# untitled.net
KiCad netlist of a schematic drawn in EAGLE
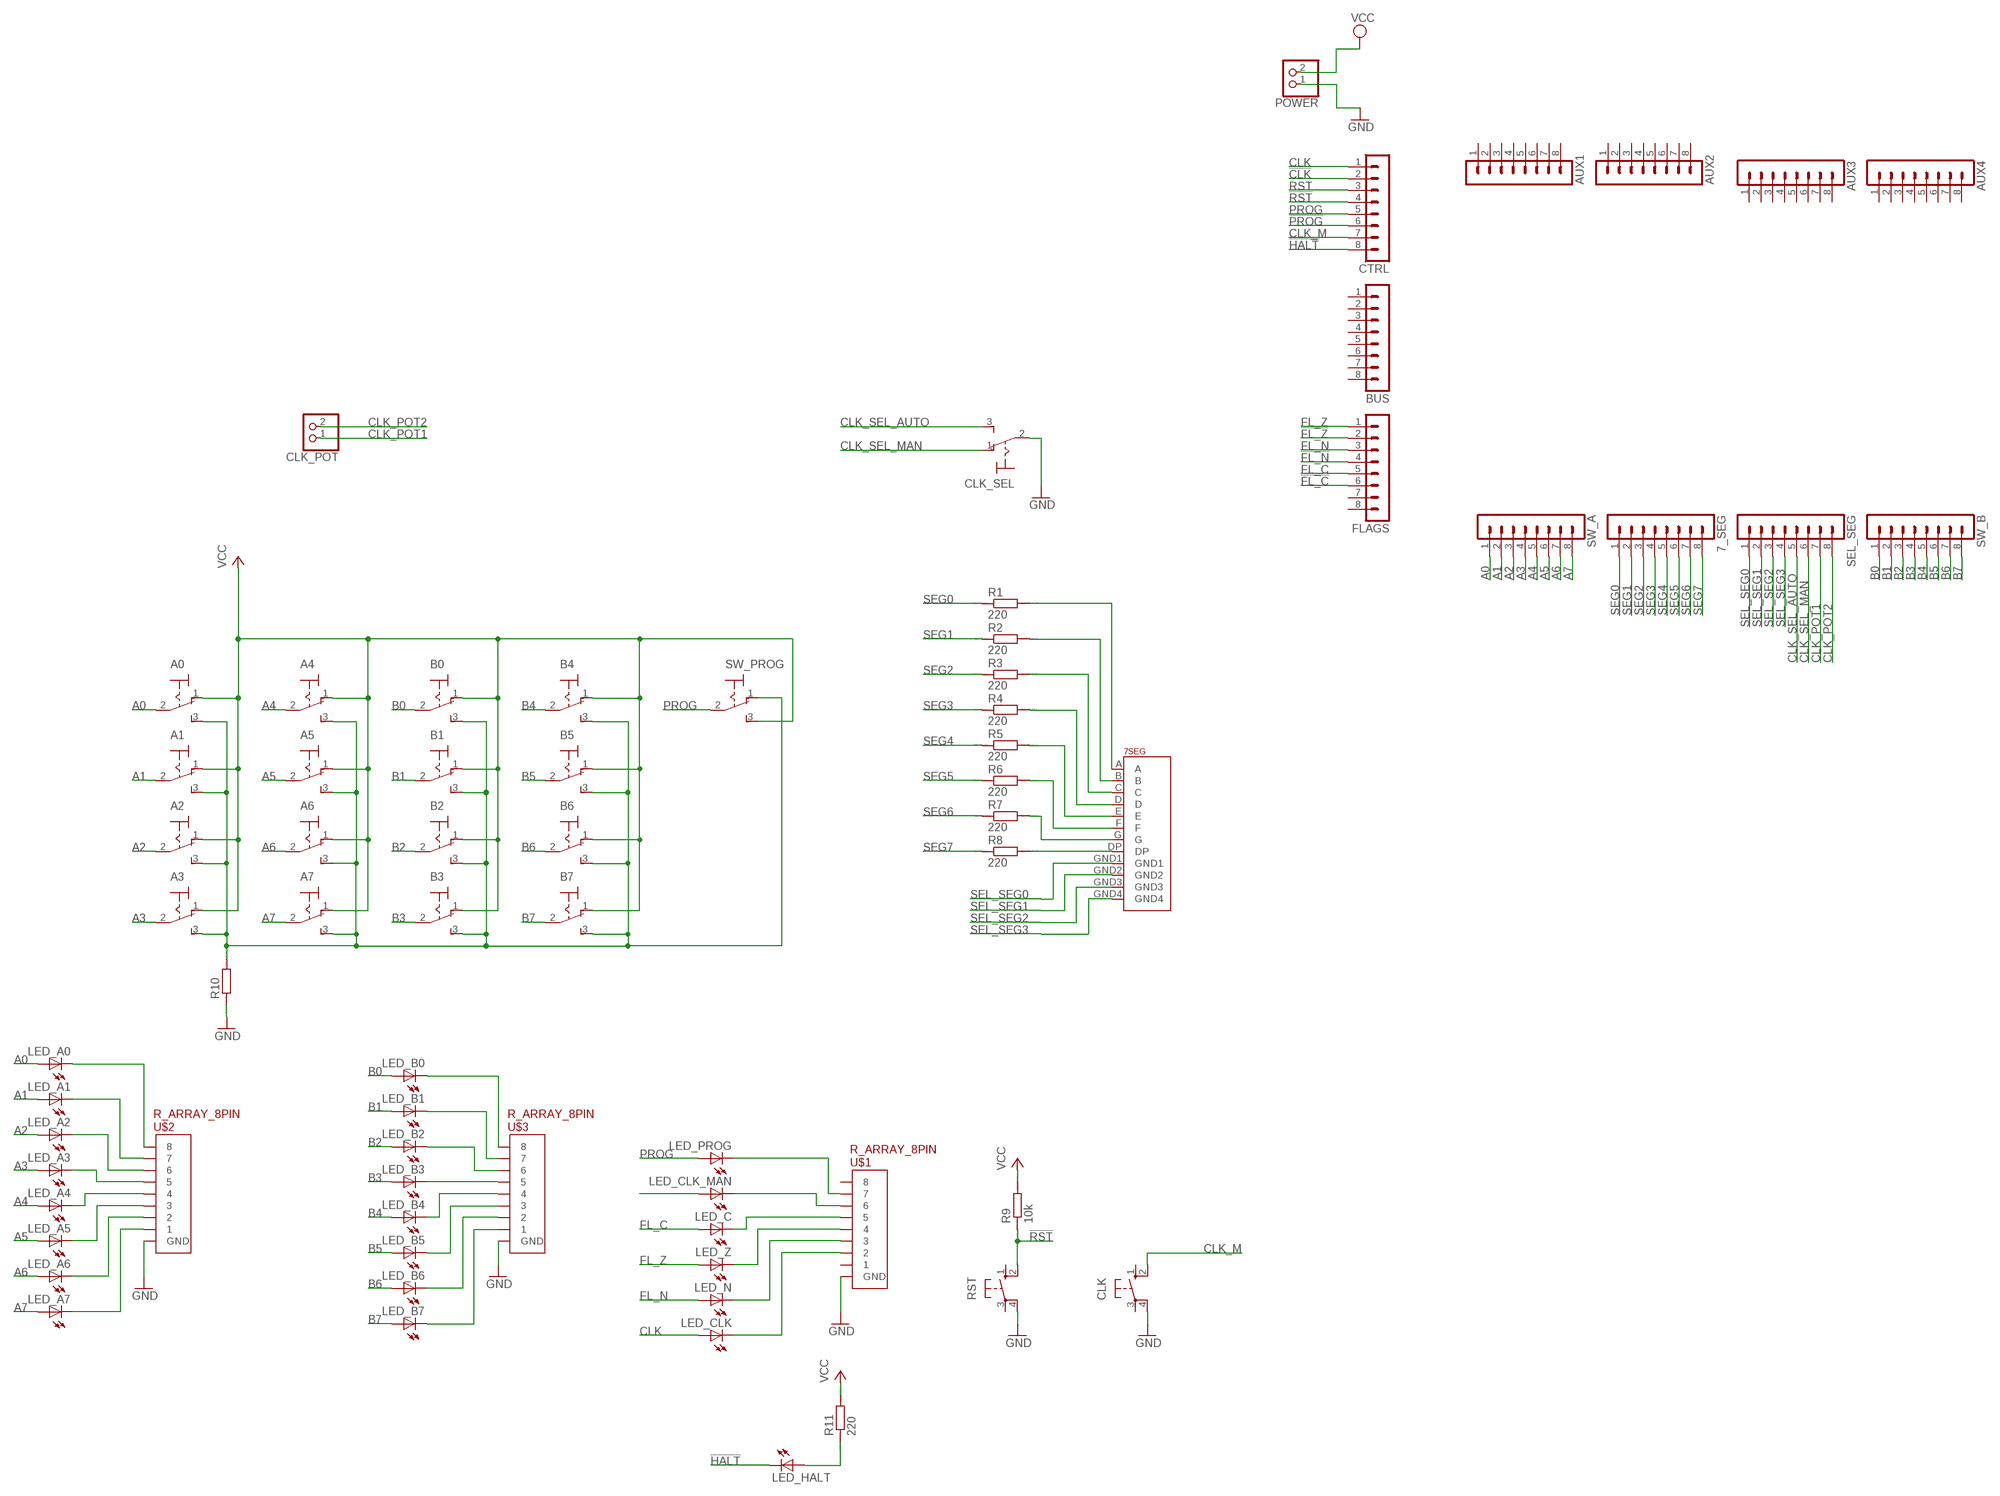
[diagram p0: schematic, sheet 1]

(export (version "E")
  (design (tool "Eeschema 10.0.6"))
  (components
    (comp (ref "7SEG")
      (value "7SEGX4")
      (footprint "eagle-import:7SEGX4")
      (libsource (lib "eagle-import") (part "7SEGX4"))
    )
    (comp (ref "7_SEG")
      (value "MA08-1")
      (footprint "eagle-import:MA08-1")
      (libsource (lib "eagle-import") (part "MA08-1"))
    )
    (comp (ref "A0")
      (value "M9040P")
      (footprint "eagle-import:M9040P")
      (libsource (lib "eagle-import") (part "M9040P"))
    )
    (comp (ref "A1")
      (value "M9040P")
      (footprint "eagle-import:M9040P")
      (libsource (lib "eagle-import") (part "M9040P"))
    )
    (comp (ref "A2")
      (value "M9040P")
      (footprint "eagle-import:M9040P")
      (libsource (lib "eagle-import") (part "M9040P"))
    )
    (comp (ref "A3")
      (value "M9040P")
      (footprint "eagle-import:M9040P")
      (libsource (lib "eagle-import") (part "M9040P"))
    )
    (comp (ref "A4")
      (value "M9040P")
      (footprint "eagle-import:M9040P")
      (libsource (lib "eagle-import") (part "M9040P"))
    )
    (comp (ref "A5")
      (value "M9040P")
      (footprint "eagle-import:M9040P")
      (libsource (lib "eagle-import") (part "M9040P"))
    )
    (comp (ref "A6")
      (value "M9040P")
      (footprint "eagle-import:M9040P")
      (libsource (lib "eagle-import") (part "M9040P"))
    )
    (comp (ref "A7")
      (value "M9040P")
      (footprint "eagle-import:M9040P")
      (libsource (lib "eagle-import") (part "M9040P"))
    )
    (comp (ref "AUX1")
      (value "MA08-1")
      (footprint "eagle-import:MA08-1")
      (libsource (lib "eagle-import") (part "MA08-1"))
    )
    (comp (ref "AUX2")
      (value "MA08-1")
      (footprint "eagle-import:MA08-1")
      (libsource (lib "eagle-import") (part "MA08-1"))
    )
    (comp (ref "AUX3")
      (value "MA08-1")
      (footprint "eagle-import:MA08-1")
      (libsource (lib "eagle-import") (part "MA08-1"))
    )
    (comp (ref "AUX4")
      (value "MA08-1")
      (footprint "eagle-import:MA08-1")
      (libsource (lib "eagle-import") (part "MA08-1"))
    )
    (comp (ref "B0")
      (value "M9040P")
      (footprint "eagle-import:M9040P")
      (libsource (lib "eagle-import") (part "M9040P"))
    )
    (comp (ref "B1")
      (value "M9040P")
      (footprint "eagle-import:M9040P")
      (libsource (lib "eagle-import") (part "M9040P"))
    )
    (comp (ref "B2")
      (value "M9040P")
      (footprint "eagle-import:M9040P")
      (libsource (lib "eagle-import") (part "M9040P"))
    )
    (comp (ref "B3")
      (value "M9040P")
      (footprint "eagle-import:M9040P")
      (libsource (lib "eagle-import") (part "M9040P"))
    )
    (comp (ref "B4")
      (value "M9040P")
      (footprint "eagle-import:M9040P")
      (libsource (lib "eagle-import") (part "M9040P"))
    )
    (comp (ref "B5")
      (value "M9040P")
      (footprint "eagle-import:M9040P")
      (libsource (lib "eagle-import") (part "M9040P"))
    )
    (comp (ref "B6")
      (value "M9040P")
      (footprint "eagle-import:M9040P")
      (libsource (lib "eagle-import") (part "M9040P"))
    )
    (comp (ref "B7")
      (value "M9040P")
      (footprint "eagle-import:M9040P")
      (libsource (lib "eagle-import") (part "M9040P"))
    )
    (comp (ref "BUS")
      (value "MA08-1")
      (footprint "eagle-import:MA08-1")
      (libsource (lib "eagle-import") (part "MA08-1"))
    )
    (comp (ref "CLK")
      (value "10-XX")
      (footprint "eagle-import:B3F-10XX")
      (fields (field (name "MPN") "B3F-1000"))
      (libsource (lib "eagle-import") (part "10-XX"))
    )
    (comp (ref "CLK_POT")
      (value "PINHD-1X2")
      (footprint "eagle-import:1X02")
      (libsource (lib "eagle-import") (part "PINHD-1X2"))
    )
    (comp (ref "CLK_SEL")
      (value "M9040P")
      (footprint "eagle-import:M9040P")
      (libsource (lib "eagle-import") (part "M9040P"))
    )
    (comp (ref "CTRL")
      (value "MA08-1")
      (footprint "eagle-import:MA08-1")
      (libsource (lib "eagle-import") (part "MA08-1"))
    )
    (comp (ref "FLAGS")
      (value "MA08-1")
      (footprint "eagle-import:MA08-1")
      (libsource (lib "eagle-import") (part "MA08-1"))
    )
    (comp (ref "LED_A0")
      (value "LED3MM")
      (footprint "eagle-import:LED3MM")
      (libsource (lib "eagle-import") (part "LED3MM"))
    )
    (comp (ref "LED_A1")
      (value "LED3MM")
      (footprint "eagle-import:LED3MM")
      (libsource (lib "eagle-import") (part "LED3MM"))
    )
    (comp (ref "LED_A2")
      (value "LED3MM")
      (footprint "eagle-import:LED3MM")
      (libsource (lib "eagle-import") (part "LED3MM"))
    )
    (comp (ref "LED_A3")
      (value "LED3MM")
      (footprint "eagle-import:LED3MM")
      (libsource (lib "eagle-import") (part "LED3MM"))
    )
    (comp (ref "LED_A4")
      (value "LED3MM")
      (footprint "eagle-import:LED3MM")
      (libsource (lib "eagle-import") (part "LED3MM"))
    )
    (comp (ref "LED_A5")
      (value "LED3MM")
      (footprint "eagle-import:LED3MM")
      (libsource (lib "eagle-import") (part "LED3MM"))
    )
    (comp (ref "LED_A6")
      (value "LED3MM")
      (footprint "eagle-import:LED3MM")
      (libsource (lib "eagle-import") (part "LED3MM"))
    )
    (comp (ref "LED_A7")
      (value "LED3MM")
      (footprint "eagle-import:LED3MM")
      (libsource (lib "eagle-import") (part "LED3MM"))
    )
    (comp (ref "LED_B0")
      (value "LED3MM")
      (footprint "eagle-import:LED3MM")
      (libsource (lib "eagle-import") (part "LED3MM"))
    )
    (comp (ref "LED_B1")
      (value "LED3MM")
      (footprint "eagle-import:LED3MM")
      (libsource (lib "eagle-import") (part "LED3MM"))
    )
    (comp (ref "LED_B2")
      (value "LED3MM")
      (footprint "eagle-import:LED3MM")
      (libsource (lib "eagle-import") (part "LED3MM"))
    )
    (comp (ref "LED_B3")
      (value "LED3MM")
      (footprint "eagle-import:LED3MM")
      (libsource (lib "eagle-import") (part "LED3MM"))
    )
    (comp (ref "LED_B4")
      (value "LED3MM")
      (footprint "eagle-import:LED3MM")
      (libsource (lib "eagle-import") (part "LED3MM"))
    )
    (comp (ref "LED_B5")
      (value "LED3MM")
      (footprint "eagle-import:LED3MM")
      (libsource (lib "eagle-import") (part "LED3MM"))
    )
    (comp (ref "LED_B6")
      (value "LED3MM")
      (footprint "eagle-import:LED3MM")
      (libsource (lib "eagle-import") (part "LED3MM"))
    )
    (comp (ref "LED_B7")
      (value "LED3MM")
      (footprint "eagle-import:LED3MM")
      (libsource (lib "eagle-import") (part "LED3MM"))
    )
    (comp (ref "LED_C")
      (value "LED3MM")
      (footprint "eagle-import:LED3MM")
      (libsource (lib "eagle-import") (part "LED3MM"))
    )
    (comp (ref "LED_CLK")
      (value "LED3MM")
      (footprint "eagle-import:LED3MM")
      (libsource (lib "eagle-import") (part "LED3MM"))
    )
    (comp (ref "LED_CLK_MAN")
      (value "LED3MM")
      (footprint "eagle-import:LED3MM")
      (libsource (lib "eagle-import") (part "LED3MM"))
    )
    (comp (ref "LED_HALT")
      (value "LED3MM")
      (footprint "eagle-import:LED3MM")
      (libsource (lib "eagle-import") (part "LED3MM"))
    )
    (comp (ref "LED_N")
      (value "LED3MM")
      (footprint "eagle-import:LED3MM")
      (libsource (lib "eagle-import") (part "LED3MM"))
    )
    (comp (ref "LED_PROG")
      (value "LED3MM")
      (footprint "eagle-import:LED3MM")
      (libsource (lib "eagle-import") (part "LED3MM"))
    )
    (comp (ref "LED_Z")
      (value "LED3MM")
      (footprint "eagle-import:LED3MM")
      (libsource (lib "eagle-import") (part "LED3MM"))
    )
    (comp (ref "POWER")
      (value "PINHD-1X2")
      (footprint "eagle-import:1X02")
      (libsource (lib "eagle-import") (part "PINHD-1X2"))
    )
    (comp (ref "R1")
      (value "220")
      (footprint "eagle-import:0207_10")
      (libsource (lib "eagle-import") (part "R0207/10"))
    )
    (comp (ref "R2")
      (value "220")
      (footprint "eagle-import:0207_10")
      (libsource (lib "eagle-import") (part "R0207/10"))
    )
    (comp (ref "R3")
      (value "220")
      (footprint "eagle-import:0207_10")
      (libsource (lib "eagle-import") (part "R0207/10"))
    )
    (comp (ref "R4")
      (value "220")
      (footprint "eagle-import:0207_10")
      (libsource (lib "eagle-import") (part "R0207/10"))
    )
    (comp (ref "R5")
      (value "220")
      (footprint "eagle-import:0207_10")
      (libsource (lib "eagle-import") (part "R0207/10"))
    )
    (comp (ref "R6")
      (value "220")
      (footprint "eagle-import:0207_10")
      (libsource (lib "eagle-import") (part "R0207/10"))
    )
    (comp (ref "R7")
      (value "220")
      (footprint "eagle-import:0207_10")
      (libsource (lib "eagle-import") (part "R0207/10"))
    )
    (comp (ref "R8")
      (value "220")
      (footprint "eagle-import:0207_10")
      (libsource (lib "eagle-import") (part "R0207/10"))
    )
    (comp (ref "R9")
      (value "10k")
      (footprint "eagle-import:0207_10")
      (libsource (lib "eagle-import") (part "R0207/10"))
    )
    (comp (ref "R10")
      (value "R0207/10")
      (footprint "eagle-import:0207_10")
      (libsource (lib "eagle-import") (part "R0207/10"))
    )
    (comp (ref "R11")
      (value "220")
      (footprint "eagle-import:0207_10")
      (libsource (lib "eagle-import") (part "R0207/10"))
    )
    (comp (ref "RST")
      (value "10-XX")
      (footprint "eagle-import:B3F-10XX")
      (fields (field (name "MPN") "B3F-1000"))
      (libsource (lib "eagle-import") (part "10-XX"))
    )
    (comp (ref "SEL_SEG")
      (value "MA08-1")
      (footprint "eagle-import:MA08-1")
      (libsource (lib "eagle-import") (part "MA08-1"))
    )
    (comp (ref "SW_A")
      (value "MA08-1")
      (footprint "eagle-import:MA08-1")
      (libsource (lib "eagle-import") (part "MA08-1"))
    )
    (comp (ref "SW_B")
      (value "MA08-1")
      (footprint "eagle-import:MA08-1")
      (libsource (lib "eagle-import") (part "MA08-1"))
    )
    (comp (ref "SW_PROG")
      (value "M9040P")
      (footprint "eagle-import:M9040P")
      (libsource (lib "eagle-import") (part "M9040P"))
    )
    (comp (ref "U$1")
      (value "R_ARRAY_8PIN")
      (footprint "eagle-import:R_ARRAY_8PIN")
      (libsource (lib "eagle-import") (part "R_ARRAY_8PIN"))
    )
    (comp (ref "U$2")
      (value "R_ARRAY_8PIN")
      (footprint "eagle-import:R_ARRAY_8PIN")
      (libsource (lib "eagle-import") (part "R_ARRAY_8PIN"))
    )
    (comp (ref "U$3")
      (value "R_ARRAY_8PIN")
      (footprint "eagle-import:R_ARRAY_8PIN")
      (libsource (lib "eagle-import") (part "R_ARRAY_8PIN"))
    )
  )
  (nets
    (net (code "1") (name "/A0") (class "Default")
      (node (ref "A0") (pin "2") (pinfunction "P_2") (pintype "passive"))
      (node (ref "LED_A0") (pin "A") (pinfunction "A_A") (pintype "passive"))
      (node (ref "SW_A") (pin "1") (pinfunction "1_1") (pintype "passive"))
    )
    (net (code "2") (name "/A1") (class "Default")
      (node (ref "A1") (pin "2") (pinfunction "P_2") (pintype "passive"))
      (node (ref "LED_A1") (pin "A") (pinfunction "A_A") (pintype "passive"))
      (node (ref "SW_A") (pin "2") (pinfunction "2_2") (pintype "passive"))
    )
    (net (code "3") (name "/A2") (class "Default")
      (node (ref "A2") (pin "2") (pinfunction "P_2") (pintype "passive"))
      (node (ref "LED_A2") (pin "A") (pinfunction "A_A") (pintype "passive"))
      (node (ref "SW_A") (pin "3") (pinfunction "3_3") (pintype "passive"))
    )
    (net (code "4") (name "/A3") (class "Default")
      (node (ref "A3") (pin "2") (pinfunction "P_2") (pintype "passive"))
      (node (ref "LED_A3") (pin "A") (pinfunction "A_A") (pintype "passive"))
      (node (ref "SW_A") (pin "4") (pinfunction "4_4") (pintype "passive"))
    )
    (net (code "5") (name "/A4") (class "Default")
      (node (ref "A4") (pin "2") (pinfunction "P_2") (pintype "passive"))
      (node (ref "LED_A4") (pin "A") (pinfunction "A_A") (pintype "passive"))
      (node (ref "SW_A") (pin "5") (pinfunction "5_5") (pintype "passive"))
    )
    (net (code "6") (name "/A5") (class "Default")
      (node (ref "A5") (pin "2") (pinfunction "P_2") (pintype "passive"))
      (node (ref "LED_A5") (pin "A") (pinfunction "A_A") (pintype "passive"))
      (node (ref "SW_A") (pin "6") (pinfunction "6_6") (pintype "passive"))
    )
    (net (code "7") (name "/A6") (class "Default")
      (node (ref "A6") (pin "2") (pinfunction "P_2") (pintype "passive"))
      (node (ref "LED_A6") (pin "A") (pinfunction "A_A") (pintype "passive"))
      (node (ref "SW_A") (pin "7") (pinfunction "7_7") (pintype "passive"))
    )
    (net (code "8") (name "/A7") (class "Default")
      (node (ref "A7") (pin "2") (pinfunction "P_2") (pintype "passive"))
      (node (ref "LED_A7") (pin "A") (pinfunction "A_A") (pintype "passive"))
      (node (ref "SW_A") (pin "8") (pinfunction "8_8") (pintype "passive"))
    )
    (net (code "9") (name "/B0") (class "Default")
      (node (ref "B0") (pin "2") (pinfunction "P_2") (pintype "passive"))
      (node (ref "LED_B0") (pin "A") (pinfunction "A_A") (pintype "passive"))
      (node (ref "SW_B") (pin "1") (pinfunction "1_1") (pintype "passive"))
    )
    (net (code "10") (name "/B1") (class "Default")
      (node (ref "B1") (pin "2") (pinfunction "P_2") (pintype "passive"))
      (node (ref "LED_B1") (pin "A") (pinfunction "A_A") (pintype "passive"))
      (node (ref "SW_B") (pin "2") (pinfunction "2_2") (pintype "passive"))
    )
    (net (code "11") (name "/B2") (class "Default")
      (node (ref "B2") (pin "2") (pinfunction "P_2") (pintype "passive"))
      (node (ref "LED_B2") (pin "A") (pinfunction "A_A") (pintype "passive"))
      (node (ref "SW_B") (pin "3") (pinfunction "3_3") (pintype "passive"))
    )
    (net (code "12") (name "/B3") (class "Default")
      (node (ref "B3") (pin "2") (pinfunction "P_2") (pintype "passive"))
      (node (ref "LED_B3") (pin "A") (pinfunction "A_A") (pintype "passive"))
      (node (ref "SW_B") (pin "4") (pinfunction "4_4") (pintype "passive"))
    )
    (net (code "13") (name "/B4") (class "Default")
      (node (ref "B4") (pin "2") (pinfunction "P_2") (pintype "passive"))
      (node (ref "LED_B4") (pin "A") (pinfunction "A_A") (pintype "passive"))
      (node (ref "SW_B") (pin "5") (pinfunction "5_5") (pintype "passive"))
    )
    (net (code "14") (name "/B5") (class "Default")
      (node (ref "B5") (pin "2") (pinfunction "P_2") (pintype "passive"))
      (node (ref "LED_B5") (pin "A") (pinfunction "A_A") (pintype "passive"))
      (node (ref "SW_B") (pin "6") (pinfunction "6_6") (pintype "passive"))
    )
    (net (code "15") (name "/B6") (class "Default")
      (node (ref "B6") (pin "2") (pinfunction "P_2") (pintype "passive"))
      (node (ref "LED_B6") (pin "A") (pinfunction "A_A") (pintype "passive"))
      (node (ref "SW_B") (pin "7") (pinfunction "7_7") (pintype "passive"))
    )
    (net (code "16") (name "/B7") (class "Default")
      (node (ref "B7") (pin "2") (pinfunction "P_2") (pintype "passive"))
      (node (ref "LED_B7") (pin "A") (pinfunction "A_A") (pintype "passive"))
      (node (ref "SW_B") (pin "8") (pinfunction "8_8") (pintype "passive"))
    )
    (net (code "17") (name "/CLK") (class "Default")
      (node (ref "CTRL") (pin "1") (pinfunction "1_1") (pintype "passive"))
      (node (ref "LED_CLK") (pin "A") (pinfunction "A_A") (pintype "passive"))
    )
    (net (code "18") (name "/CLK_M") (class "Default")
      (node (ref "CLK") (pin "2") (pinfunction "S1_2") (pintype "passive"))
      (node (ref "CTRL") (pin "7") (pinfunction "7_7") (pintype "passive"))
    )
    (net (code "19") (name "/CLK_POT1") (class "Default")
      (node (ref "CLK_POT") (pin "1") (pinfunction "1_1") (pintype "passive"))
      (node (ref "SEL_SEG") (pin "7") (pinfunction "7_7") (pintype "passive"))
    )
    (net (code "20") (name "/CLK_POT2") (class "Default")
      (node (ref "CLK_POT") (pin "2") (pinfunction "2_2") (pintype "passive"))
      (node (ref "SEL_SEG") (pin "8") (pinfunction "8_8") (pintype "passive"))
    )
    (net (code "21") (name "/CLK_SEL_AUTO") (class "Default")
      (node (ref "CLK_SEL") (pin "3") (pinfunction "S_3") (pintype "passive"))
      (node (ref "SEL_SEG") (pin "5") (pinfunction "5_5") (pintype "passive"))
    )
    (net (code "22") (name "/CLK_SEL_MAN") (class "Default")
      (node (ref "CLK_SEL") (pin "1") (pinfunction "O_1") (pintype "passive"))
      (node (ref "SEL_SEG") (pin "6") (pinfunction "6_6") (pintype "passive"))
    )
    (net (code "23") (name "/FL_C") (class "Default")
      (node (ref "FLAGS") (pin "5") (pinfunction "5_5") (pintype "passive"))
      (node (ref "LED_C") (pin "A") (pinfunction "A_A") (pintype "passive"))
    )
    (net (code "24") (name "/FL_N") (class "Default")
      (node (ref "FLAGS") (pin "3") (pinfunction "3_3") (pintype "passive"))
      (node (ref "LED_N") (pin "A") (pinfunction "A_A") (pintype "passive"))
    )
    (net (code "25") (name "/FL_Z") (class "Default")
      (node (ref "FLAGS") (pin "1") (pinfunction "1_1") (pintype "passive"))
      (node (ref "LED_Z") (pin "A") (pinfunction "A_A") (pintype "passive"))
    )
    (net (code "26") (name "/PROG") (class "Default")
      (node (ref "CTRL") (pin "5") (pinfunction "5_5") (pintype "passive"))
      (node (ref "LED_PROG") (pin "A") (pinfunction "A_A") (pintype "passive"))
      (node (ref "SW_PROG") (pin "2") (pinfunction "P_2") (pintype "passive"))
    )
    (net (code "27") (name "/RST") (class "Default")
      (node (ref "CTRL") (pin "3") (pinfunction "3_3") (pintype "passive"))
    )
    (net (code "28") (name "/SEG0") (class "Default")
      (node (ref "7_SEG") (pin "1") (pinfunction "1_1") (pintype "passive"))
      (node (ref "R1") (pin "1") (pinfunction "1_1") (pintype "passive"))
    )
    (net (code "29") (name "/SEG1") (class "Default")
      (node (ref "7_SEG") (pin "2") (pinfunction "2_2") (pintype "passive"))
      (node (ref "R2") (pin "1") (pinfunction "1_1") (pintype "passive"))
    )
    (net (code "30") (name "/SEG2") (class "Default")
      (node (ref "7_SEG") (pin "3") (pinfunction "3_3") (pintype "passive"))
      (node (ref "R3") (pin "1") (pinfunction "1_1") (pintype "passive"))
    )
    (net (code "31") (name "/SEG3") (class "Default")
      (node (ref "7_SEG") (pin "4") (pinfunction "4_4") (pintype "passive"))
      (node (ref "R4") (pin "1") (pinfunction "1_1") (pintype "passive"))
    )
    (net (code "32") (name "/SEG4") (class "Default")
      (node (ref "7_SEG") (pin "5") (pinfunction "5_5") (pintype "passive"))
      (node (ref "R5") (pin "1") (pinfunction "1_1") (pintype "passive"))
    )
    (net (code "33") (name "/SEG5") (class "Default")
      (node (ref "7_SEG") (pin "6") (pinfunction "6_6") (pintype "passive"))
      (node (ref "R6") (pin "1") (pinfunction "1_1") (pintype "passive"))
    )
    (net (code "34") (name "/SEG6") (class "Default")
      (node (ref "7_SEG") (pin "7") (pinfunction "7_7") (pintype "passive"))
      (node (ref "R7") (pin "1") (pinfunction "1_1") (pintype "passive"))
    )
    (net (code "35") (name "/SEG7") (class "Default")
      (node (ref "7_SEG") (pin "8") (pinfunction "8_8") (pintype "passive"))
      (node (ref "R8") (pin "1") (pinfunction "1_1") (pintype "passive"))
    )
    (net (code "36") (name "/SEL_SEG0") (class "Default")
      (node (ref "7SEG") (pin "GND1") (pinfunction "GND1_GND1") (pintype "bidirectional"))
      (node (ref "SEL_SEG") (pin "1") (pinfunction "1_1") (pintype "passive"))
    )
    (net (code "37") (name "/SEL_SEG1") (class "Default")
      (node (ref "7SEG") (pin "GND2") (pinfunction "GND2_GND2") (pintype "bidirectional"))
      (node (ref "SEL_SEG") (pin "2") (pinfunction "2_2") (pintype "passive"))
    )
    (net (code "38") (name "/SEL_SEG2") (class "Default")
      (node (ref "7SEG") (pin "GND3") (pinfunction "GND3_GND3") (pintype "bidirectional"))
      (node (ref "SEL_SEG") (pin "3") (pinfunction "3_3") (pintype "passive"))
    )
    (net (code "39") (name "/SEL_SEG3") (class "Default")
      (node (ref "7SEG") (pin "GND4") (pinfunction "GND4_GND4") (pintype "bidirectional"))
      (node (ref "SEL_SEG") (pin "4") (pinfunction "4_4") (pintype "passive"))
    )
    (net (code "40") (name "/~{CLK}") (class "Default")
      (node (ref "CTRL") (pin "2") (pinfunction "2_2") (pintype "passive"))
    )
    (net (code "41") (name "/~{FL_C}") (class "Default")
      (node (ref "FLAGS") (pin "6") (pinfunction "6_6") (pintype "passive"))
    )
    (net (code "42") (name "/~{FL_N}") (class "Default")
      (node (ref "FLAGS") (pin "4") (pinfunction "4_4") (pintype "passive"))
    )
    (net (code "43") (name "/~{FL_Z}") (class "Default")
      (node (ref "FLAGS") (pin "2") (pinfunction "2_2") (pintype "passive"))
    )
    (net (code "44") (name "/~{HALT}") (class "Default")
      (node (ref "CTRL") (pin "8") (pinfunction "8_8") (pintype "passive"))
      (node (ref "LED_HALT") (pin "K") (pinfunction "C_K") (pintype "passive"))
    )
    (net (code "45") (name "/~{PROG}") (class "Default")
      (node (ref "CTRL") (pin "6") (pinfunction "6_6") (pintype "passive"))
    )
    (net (code "46") (name "/~{RST}") (class "Default")
      (node (ref "CTRL") (pin "4") (pinfunction "4_4") (pintype "passive"))
      (node (ref "R9") (pin "1") (pinfunction "1_1") (pintype "passive"))
      (node (ref "RST") (pin "2") (pinfunction "S1_2") (pintype "passive"))
    )
    (net (code "47") (name "GND") (class "Default")
      (node (ref "CLK") (pin "4") (pinfunction "P1_4") (pintype "passive"))
      (node (ref "CLK_SEL") (pin "2") (pinfunction "P_2") (pintype "passive"))
      (node (ref "POWER") (pin "1") (pinfunction "1_1") (pintype "passive"))
      (node (ref "R10") (pin "1") (pinfunction "1_1") (pintype "passive"))
      (node (ref "RST") (pin "4") (pinfunction "P1_4") (pintype "passive"))
      (node (ref "U$1") (pin "GND") (pinfunction "GND_GND") (pintype "bidirectional"))
      (node (ref "U$2") (pin "GND") (pinfunction "GND_GND") (pintype "bidirectional"))
      (node (ref "U$3") (pin "GND") (pinfunction "GND_GND") (pintype "bidirectional"))
    )
    (net (code "48") (name "Net-(7SEG-PadA)") (class "Default")
      (node (ref "7SEG") (pin "A") (pinfunction "A_A") (pintype "bidirectional"))
      (node (ref "R1") (pin "2") (pinfunction "2_2") (pintype "passive"))
    )
    (net (code "49") (name "Net-(7SEG-PadB)") (class "Default")
      (node (ref "7SEG") (pin "B") (pinfunction "B_B") (pintype "bidirectional"))
      (node (ref "R2") (pin "2") (pinfunction "2_2") (pintype "passive"))
    )
    (net (code "50") (name "Net-(7SEG-PadC)") (class "Default")
      (node (ref "7SEG") (pin "C") (pinfunction "C_C") (pintype "bidirectional"))
      (node (ref "R3") (pin "2") (pinfunction "2_2") (pintype "passive"))
    )
    (net (code "51") (name "Net-(7SEG-PadD)") (class "Default")
      (node (ref "7SEG") (pin "D") (pinfunction "D_D") (pintype "bidirectional"))
      (node (ref "R4") (pin "2") (pinfunction "2_2") (pintype "passive"))
    )
    (net (code "52") (name "Net-(7SEG-PadDP)") (class "Default")
      (node (ref "7SEG") (pin "DP") (pinfunction "DP_DP") (pintype "bidirectional"))
      (node (ref "R8") (pin "2") (pinfunction "2_2") (pintype "passive"))
    )
    (net (code "53") (name "Net-(7SEG-PadE)") (class "Default")
      (node (ref "7SEG") (pin "E") (pinfunction "E_E") (pintype "bidirectional"))
      (node (ref "R5") (pin "2") (pinfunction "2_2") (pintype "passive"))
    )
    (net (code "54") (name "Net-(7SEG-PadF)") (class "Default")
      (node (ref "7SEG") (pin "F") (pinfunction "F_F") (pintype "bidirectional"))
      (node (ref "R6") (pin "2") (pinfunction "2_2") (pintype "passive"))
    )
    (net (code "55") (name "Net-(7SEG-PadG)") (class "Default")
      (node (ref "7SEG") (pin "G") (pinfunction "G_G") (pintype "bidirectional"))
      (node (ref "R7") (pin "2") (pinfunction "2_2") (pintype "passive"))
    )
    (net (code "56") (name "Net-(A0-S)") (class "Default")
      (node (ref "A0") (pin "3") (pinfunction "S_3") (pintype "passive"))
      (node (ref "A1") (pin "3") (pinfunction "S_3") (pintype "passive"))
      (node (ref "A2") (pin "3") (pinfunction "S_3") (pintype "passive"))
      (node (ref "A3") (pin "3") (pinfunction "S_3") (pintype "passive"))
      (node (ref "A4") (pin "3") (pinfunction "S_3") (pintype "passive"))
      (node (ref "A5") (pin "3") (pinfunction "S_3") (pintype "passive"))
      (node (ref "A6") (pin "3") (pinfunction "S_3") (pintype "passive"))
      (node (ref "A7") (pin "3") (pinfunction "S_3") (pintype "passive"))
      (node (ref "B0") (pin "3") (pinfunction "S_3") (pintype "passive"))
      (node (ref "B1") (pin "3") (pinfunction "S_3") (pintype "passive"))
      (node (ref "B2") (pin "3") (pinfunction "S_3") (pintype "passive"))
      (node (ref "B3") (pin "3") (pinfunction "S_3") (pintype "passive"))
      (node (ref "B4") (pin "3") (pinfunction "S_3") (pintype "passive"))
      (node (ref "B5") (pin "3") (pinfunction "S_3") (pintype "passive"))
      (node (ref "B6") (pin "3") (pinfunction "S_3") (pintype "passive"))
      (node (ref "B7") (pin "3") (pinfunction "S_3") (pintype "passive"))
      (node (ref "R10") (pin "2") (pinfunction "2_2") (pintype "passive"))
      (node (ref "SW_PROG") (pin "1") (pinfunction "O_1") (pintype "passive"))
    )
    (net (code "57") (name "Net-(LED_A0-C)") (class "Default")
      (node (ref "LED_A0") (pin "K") (pinfunction "C_K") (pintype "passive"))
      (node (ref "U$2") (pin "8") (pinfunction "8_8") (pintype "bidirectional"))
    )
    (net (code "58") (name "Net-(LED_A1-C)") (class "Default")
      (node (ref "LED_A1") (pin "K") (pinfunction "C_K") (pintype "passive"))
      (node (ref "U$2") (pin "7") (pinfunction "7_7") (pintype "bidirectional"))
    )
    (net (code "59") (name "Net-(LED_A2-C)") (class "Default")
      (node (ref "LED_A2") (pin "K") (pinfunction "C_K") (pintype "passive"))
      (node (ref "U$2") (pin "6") (pinfunction "6_6") (pintype "bidirectional"))
    )
    (net (code "60") (name "Net-(LED_A3-C)") (class "Default")
      (node (ref "LED_A3") (pin "K") (pinfunction "C_K") (pintype "passive"))
      (node (ref "U$2") (pin "5") (pinfunction "5_5") (pintype "bidirectional"))
    )
    (net (code "61") (name "Net-(LED_A4-C)") (class "Default")
      (node (ref "LED_A4") (pin "K") (pinfunction "C_K") (pintype "passive"))
      (node (ref "U$2") (pin "4") (pinfunction "4_4") (pintype "bidirectional"))
    )
    (net (code "62") (name "Net-(LED_A5-C)") (class "Default")
      (node (ref "LED_A5") (pin "K") (pinfunction "C_K") (pintype "passive"))
      (node (ref "U$2") (pin "3") (pinfunction "3_3") (pintype "bidirectional"))
    )
    (net (code "63") (name "Net-(LED_A6-C)") (class "Default")
      (node (ref "LED_A6") (pin "K") (pinfunction "C_K") (pintype "passive"))
      (node (ref "U$2") (pin "2") (pinfunction "2_2") (pintype "bidirectional"))
    )
    (net (code "64") (name "Net-(LED_A7-C)") (class "Default")
      (node (ref "LED_A7") (pin "K") (pinfunction "C_K") (pintype "passive"))
      (node (ref "U$2") (pin "1") (pinfunction "1_1") (pintype "bidirectional"))
    )
    (net (code "65") (name "Net-(LED_B0-C)") (class "Default")
      (node (ref "LED_B0") (pin "K") (pinfunction "C_K") (pintype "passive"))
      (node (ref "U$3") (pin "8") (pinfunction "8_8") (pintype "bidirectional"))
    )
    (net (code "66") (name "Net-(LED_B1-C)") (class "Default")
      (node (ref "LED_B1") (pin "K") (pinfunction "C_K") (pintype "passive"))
      (node (ref "U$3") (pin "7") (pinfunction "7_7") (pintype "bidirectional"))
    )
    (net (code "67") (name "Net-(LED_B2-C)") (class "Default")
      (node (ref "LED_B2") (pin "K") (pinfunction "C_K") (pintype "passive"))
      (node (ref "U$3") (pin "6") (pinfunction "6_6") (pintype "bidirectional"))
    )
    (net (code "68") (name "Net-(LED_B3-C)") (class "Default")
      (node (ref "LED_B3") (pin "K") (pinfunction "C_K") (pintype "passive"))
      (node (ref "U$3") (pin "5") (pinfunction "5_5") (pintype "bidirectional"))
    )
    (net (code "69") (name "Net-(LED_B4-C)") (class "Default")
      (node (ref "LED_B4") (pin "K") (pinfunction "C_K") (pintype "passive"))
      (node (ref "U$3") (pin "4") (pinfunction "4_4") (pintype "bidirectional"))
    )
    (net (code "70") (name "Net-(LED_B5-C)") (class "Default")
      (node (ref "LED_B5") (pin "K") (pinfunction "C_K") (pintype "passive"))
      (node (ref "U$3") (pin "3") (pinfunction "3_3") (pintype "bidirectional"))
    )
    (net (code "71") (name "Net-(LED_B6-C)") (class "Default")
      (node (ref "LED_B6") (pin "K") (pinfunction "C_K") (pintype "passive"))
      (node (ref "U$3") (pin "2") (pinfunction "2_2") (pintype "bidirectional"))
    )
    (net (code "72") (name "Net-(LED_B7-C)") (class "Default")
      (node (ref "LED_B7") (pin "K") (pinfunction "C_K") (pintype "passive"))
      (node (ref "U$3") (pin "1") (pinfunction "1_1") (pintype "bidirectional"))
    )
    (net (code "73") (name "Net-(LED_C-C)") (class "Default")
      (node (ref "LED_C") (pin "K") (pinfunction "C_K") (pintype "passive"))
      (node (ref "U$1") (pin "5") (pinfunction "5_5") (pintype "bidirectional"))
    )
    (net (code "74") (name "Net-(LED_CLK-C)") (class "Default")
      (node (ref "LED_CLK") (pin "K") (pinfunction "C_K") (pintype "passive"))
      (node (ref "U$1") (pin "2") (pinfunction "2_2") (pintype "bidirectional"))
    )
    (net (code "75") (name "Net-(LED_CLK_MAN-C)") (class "Default")
      (node (ref "LED_CLK_MAN") (pin "K") (pinfunction "C_K") (pintype "passive"))
      (node (ref "U$1") (pin "6") (pinfunction "6_6") (pintype "bidirectional"))
    )
    (net (code "76") (name "Net-(LED_HALT-PadA)") (class "Default")
      (node (ref "LED_HALT") (pin "A") (pinfunction "A_A") (pintype "passive"))
      (node (ref "R11") (pin "1") (pinfunction "1_1") (pintype "passive"))
    )
    (net (code "77") (name "Net-(LED_N-C)") (class "Default")
      (node (ref "LED_N") (pin "K") (pinfunction "C_K") (pintype "passive"))
      (node (ref "U$1") (pin "3") (pinfunction "3_3") (pintype "bidirectional"))
    )
    (net (code "78") (name "Net-(LED_PROG-C)") (class "Default")
      (node (ref "LED_PROG") (pin "K") (pinfunction "C_K") (pintype "passive"))
      (node (ref "U$1") (pin "7") (pinfunction "7_7") (pintype "bidirectional"))
    )
    (net (code "79") (name "Net-(LED_Z-C)") (class "Default")
      (node (ref "LED_Z") (pin "K") (pinfunction "C_K") (pintype "passive"))
      (node (ref "U$1") (pin "4") (pinfunction "4_4") (pintype "bidirectional"))
    )
    (net (code "80") (name "VCC") (class "Default")
      (node (ref "A0") (pin "1") (pinfunction "O_1") (pintype "passive"))
      (node (ref "A1") (pin "1") (pinfunction "O_1") (pintype "passive"))
      (node (ref "A2") (pin "1") (pinfunction "O_1") (pintype "passive"))
      (node (ref "A3") (pin "1") (pinfunction "O_1") (pintype "passive"))
      (node (ref "A4") (pin "1") (pinfunction "O_1") (pintype "passive"))
      (node (ref "A5") (pin "1") (pinfunction "O_1") (pintype "passive"))
      (node (ref "A6") (pin "1") (pinfunction "O_1") (pintype "passive"))
      (node (ref "A7") (pin "1") (pinfunction "O_1") (pintype "passive"))
      (node (ref "B0") (pin "1") (pinfunction "O_1") (pintype "passive"))
      (node (ref "B1") (pin "1") (pinfunction "O_1") (pintype "passive"))
      (node (ref "B2") (pin "1") (pinfunction "O_1") (pintype "passive"))
      (node (ref "B3") (pin "1") (pinfunction "O_1") (pintype "passive"))
      (node (ref "B4") (pin "1") (pinfunction "O_1") (pintype "passive"))
      (node (ref "B5") (pin "1") (pinfunction "O_1") (pintype "passive"))
      (node (ref "B6") (pin "1") (pinfunction "O_1") (pintype "passive"))
      (node (ref "B7") (pin "1") (pinfunction "O_1") (pintype "passive"))
      (node (ref "POWER") (pin "2") (pinfunction "2_2") (pintype "passive"))
      (node (ref "R11") (pin "2") (pinfunction "2_2") (pintype "passive"))
      (node (ref "R9") (pin "2") (pinfunction "2_2") (pintype "passive"))
      (node (ref "SW_PROG") (pin "3") (pinfunction "S_3") (pintype "passive"))
    )
    (net (code "81") (name "unconnected-(AUX1-Pad1)") (class "Default")
      (node (ref "AUX1") (pin "1") (pinfunction "1_1") (pintype "passive"))
    )
    (net (code "82") (name "unconnected-(AUX1-Pad2)") (class "Default")
      (node (ref "AUX1") (pin "2") (pinfunction "2_2") (pintype "passive"))
    )
    (net (code "83") (name "unconnected-(AUX1-Pad3)") (class "Default")
      (node (ref "AUX1") (pin "3") (pinfunction "3_3") (pintype "passive"))
    )
    (net (code "84") (name "unconnected-(AUX1-Pad4)") (class "Default")
      (node (ref "AUX1") (pin "4") (pinfunction "4_4") (pintype "passive"))
    )
    (net (code "85") (name "unconnected-(AUX1-Pad5)") (class "Default")
      (node (ref "AUX1") (pin "5") (pinfunction "5_5") (pintype "passive"))
    )
    (net (code "86") (name "unconnected-(AUX1-Pad6)") (class "Default")
      (node (ref "AUX1") (pin "6") (pinfunction "6_6") (pintype "passive"))
    )
    (net (code "87") (name "unconnected-(AUX1-Pad7)") (class "Default")
      (node (ref "AUX1") (pin "7") (pinfunction "7_7") (pintype "passive"))
    )
    (net (code "88") (name "unconnected-(AUX1-Pad8)") (class "Default")
      (node (ref "AUX1") (pin "8") (pinfunction "8_8") (pintype "passive"))
    )
    (net (code "89") (name "unconnected-(AUX2-Pad1)") (class "Default")
      (node (ref "AUX2") (pin "1") (pinfunction "1_1") (pintype "passive"))
    )
    (net (code "90") (name "unconnected-(AUX2-Pad2)") (class "Default")
      (node (ref "AUX2") (pin "2") (pinfunction "2_2") (pintype "passive"))
    )
    (net (code "91") (name "unconnected-(AUX2-Pad3)") (class "Default")
      (node (ref "AUX2") (pin "3") (pinfunction "3_3") (pintype "passive"))
    )
    (net (code "92") (name "unconnected-(AUX2-Pad4)") (class "Default")
      (node (ref "AUX2") (pin "4") (pinfunction "4_4") (pintype "passive"))
    )
    (net (code "93") (name "unconnected-(AUX2-Pad5)") (class "Default")
      (node (ref "AUX2") (pin "5") (pinfunction "5_5") (pintype "passive"))
    )
    (net (code "94") (name "unconnected-(AUX2-Pad6)") (class "Default")
      (node (ref "AUX2") (pin "6") (pinfunction "6_6") (pintype "passive"))
    )
    (net (code "95") (name "unconnected-(AUX2-Pad7)") (class "Default")
      (node (ref "AUX2") (pin "7") (pinfunction "7_7") (pintype "passive"))
    )
    (net (code "96") (name "unconnected-(AUX2-Pad8)") (class "Default")
      (node (ref "AUX2") (pin "8") (pinfunction "8_8") (pintype "passive"))
    )
    (net (code "97") (name "unconnected-(AUX3-Pad1)") (class "Default")
      (node (ref "AUX3") (pin "1") (pinfunction "1_1") (pintype "passive"))
    )
    (net (code "98") (name "unconnected-(AUX3-Pad2)") (class "Default")
      (node (ref "AUX3") (pin "2") (pinfunction "2_2") (pintype "passive"))
    )
    (net (code "99") (name "unconnected-(AUX3-Pad3)") (class "Default")
      (node (ref "AUX3") (pin "3") (pinfunction "3_3") (pintype "passive"))
    )
    (net (code "100") (name "unconnected-(AUX3-Pad4)") (class "Default")
      (node (ref "AUX3") (pin "4") (pinfunction "4_4") (pintype "passive"))
    )
    (net (code "101") (name "unconnected-(AUX3-Pad5)") (class "Default")
      (node (ref "AUX3") (pin "5") (pinfunction "5_5") (pintype "passive"))
    )
    (net (code "102") (name "unconnected-(AUX3-Pad6)") (class "Default")
      (node (ref "AUX3") (pin "6") (pinfunction "6_6") (pintype "passive"))
    )
    (net (code "103") (name "unconnected-(AUX3-Pad7)") (class "Default")
      (node (ref "AUX3") (pin "7") (pinfunction "7_7") (pintype "passive"))
    )
    (net (code "104") (name "unconnected-(AUX3-Pad8)") (class "Default")
      (node (ref "AUX3") (pin "8") (pinfunction "8_8") (pintype "passive"))
    )
    (net (code "105") (name "unconnected-(AUX4-Pad1)") (class "Default")
      (node (ref "AUX4") (pin "1") (pinfunction "1_1") (pintype "passive"))
    )
    (net (code "106") (name "unconnected-(AUX4-Pad2)") (class "Default")
      (node (ref "AUX4") (pin "2") (pinfunction "2_2") (pintype "passive"))
    )
    (net (code "107") (name "unconnected-(AUX4-Pad3)") (class "Default")
      (node (ref "AUX4") (pin "3") (pinfunction "3_3") (pintype "passive"))
    )
    (net (code "108") (name "unconnected-(AUX4-Pad4)") (class "Default")
      (node (ref "AUX4") (pin "4") (pinfunction "4_4") (pintype "passive"))
    )
    (net (code "109") (name "unconnected-(AUX4-Pad5)") (class "Default")
      (node (ref "AUX4") (pin "5") (pinfunction "5_5") (pintype "passive"))
    )
    (net (code "110") (name "unconnected-(AUX4-Pad6)") (class "Default")
      (node (ref "AUX4") (pin "6") (pinfunction "6_6") (pintype "passive"))
    )
    (net (code "111") (name "unconnected-(AUX4-Pad7)") (class "Default")
      (node (ref "AUX4") (pin "7") (pinfunction "7_7") (pintype "passive"))
    )
    (net (code "112") (name "unconnected-(AUX4-Pad8)") (class "Default")
      (node (ref "AUX4") (pin "8") (pinfunction "8_8") (pintype "passive"))
    )
    (net (code "113") (name "unconnected-(BUS-Pad1)") (class "Default")
      (node (ref "BUS") (pin "1") (pinfunction "1_1") (pintype "passive"))
    )
    (net (code "114") (name "unconnected-(BUS-Pad2)") (class "Default")
      (node (ref "BUS") (pin "2") (pinfunction "2_2") (pintype "passive"))
    )
    (net (code "115") (name "unconnected-(BUS-Pad3)") (class "Default")
      (node (ref "BUS") (pin "3") (pinfunction "3_3") (pintype "passive"))
    )
    (net (code "116") (name "unconnected-(BUS-Pad4)") (class "Default")
      (node (ref "BUS") (pin "4") (pinfunction "4_4") (pintype "passive"))
    )
    (net (code "117") (name "unconnected-(BUS-Pad5)") (class "Default")
      (node (ref "BUS") (pin "5") (pinfunction "5_5") (pintype "passive"))
    )
    (net (code "118") (name "unconnected-(BUS-Pad6)") (class "Default")
      (node (ref "BUS") (pin "6") (pinfunction "6_6") (pintype "passive"))
    )
    (net (code "119") (name "unconnected-(BUS-Pad7)") (class "Default")
      (node (ref "BUS") (pin "7") (pinfunction "7_7") (pintype "passive"))
    )
    (net (code "120") (name "unconnected-(BUS-Pad8)") (class "Default")
      (node (ref "BUS") (pin "8") (pinfunction "8_8") (pintype "passive"))
    )
    (net (code "121") (name "unconnected-(CLK-P-Pad3)") (class "Default")
      (node (ref "CLK") (pin "3") (pinfunction "P_3") (pintype "passive"))
    )
    (net (code "122") (name "unconnected-(CLK-S-Pad1)") (class "Default")
      (node (ref "CLK") (pin "1") (pinfunction "S_1") (pintype "passive"))
    )
    (net (code "123") (name "unconnected-(FLAGS-Pad7)") (class "Default")
      (node (ref "FLAGS") (pin "7") (pinfunction "7_7") (pintype "passive"))
    )
    (net (code "124") (name "unconnected-(FLAGS-Pad8)") (class "Default")
      (node (ref "FLAGS") (pin "8") (pinfunction "8_8") (pintype "passive"))
    )
    (net (code "125") (name "unconnected-(LED_CLK_MAN-PadA)") (class "Default")
      (node (ref "LED_CLK_MAN") (pin "A") (pinfunction "A_A") (pintype "passive"))
    )
    (net (code "126") (name "unconnected-(RST-P-Pad3)") (class "Default")
      (node (ref "RST") (pin "3") (pinfunction "P_3") (pintype "passive"))
    )
    (net (code "127") (name "unconnected-(RST-S-Pad1)") (class "Default")
      (node (ref "RST") (pin "1") (pinfunction "S_1") (pintype "passive"))
    )
    (net (code "128") (name "unconnected-(U$1-Pad1)") (class "Default")
      (node (ref "U$1") (pin "1") (pinfunction "1_1") (pintype "bidirectional"))
    )
    (net (code "129") (name "unconnected-(U$1-Pad8)") (class "Default")
      (node (ref "U$1") (pin "8") (pinfunction "8_8") (pintype "bidirectional"))
    )
  )
)
